# V2.net
KiCad netlist of a schematic drawn in Altium Designer
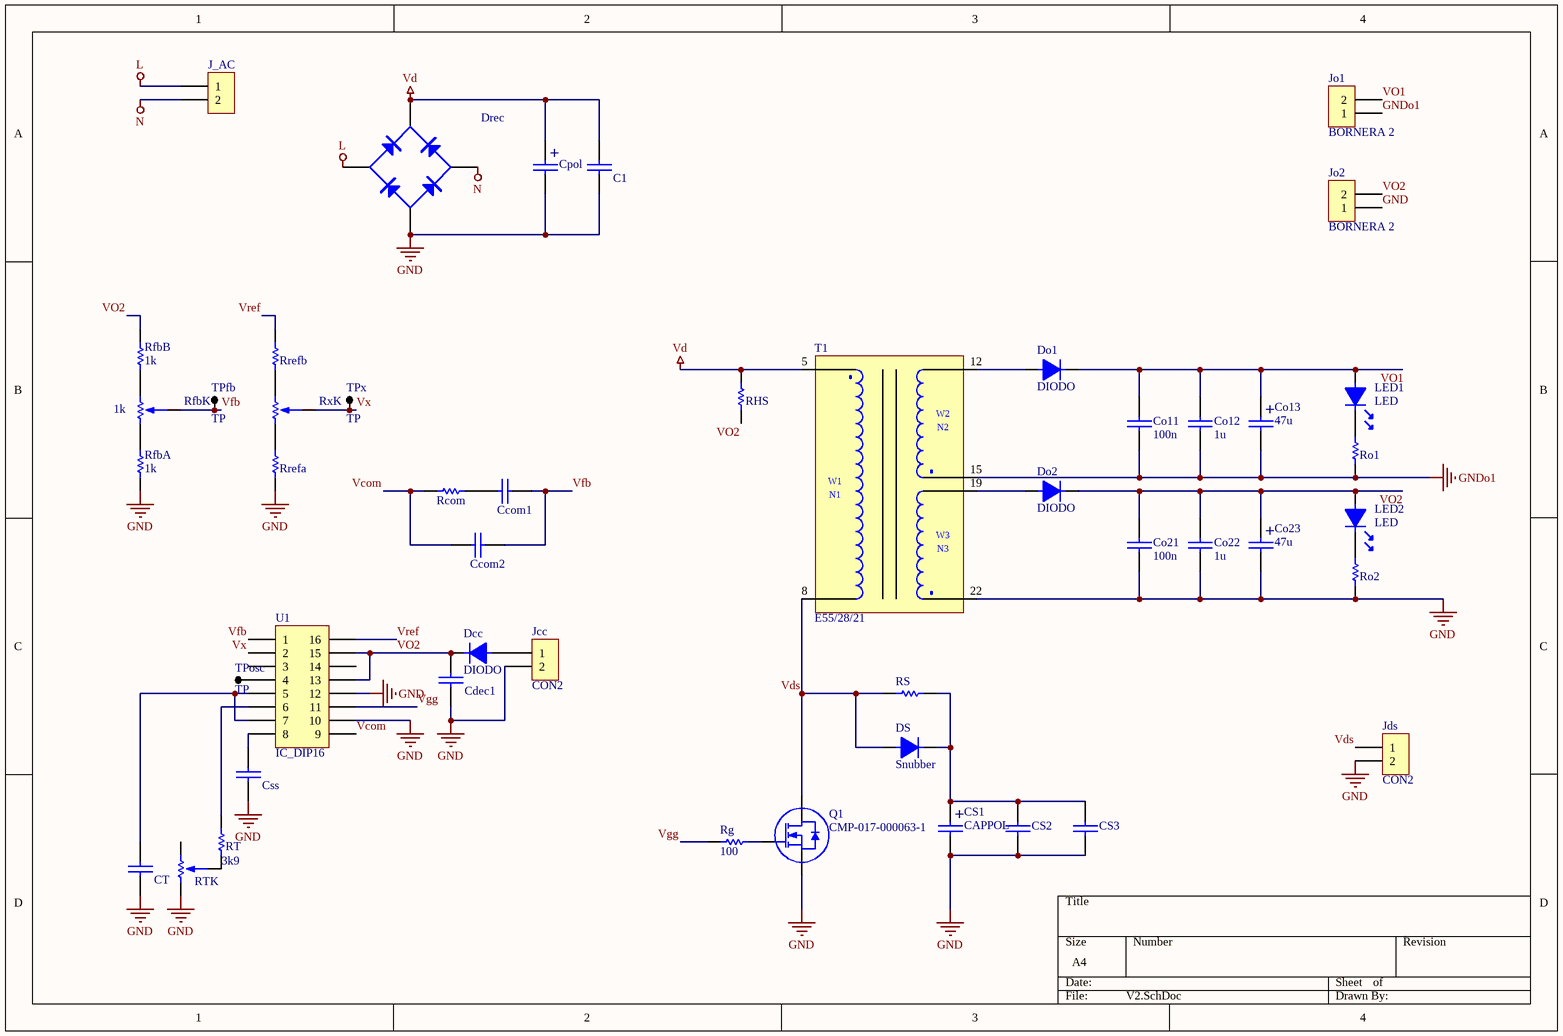
[diagram p0: V2.SchDoc]

(export (version "E")
  (design (tool "Eeschema 10.0.6"))
  (components
    (comp (ref "C1") (value "CAP") (footprint "CAP200") (libsource (lib "Victor Oh") (part "CAP")))
    (comp (ref "Ccom1") (value "CAP") (footprint "CAP200") (libsource (lib "Victor Oh") (part "CAP")))
    (comp (ref "Ccom2") (value "CAP") (footprint "CAP200") (libsource (lib "Victor Oh") (part "CAP")))
    (comp (ref "Cdec1") (value "CAP") (footprint "CAP100") (libsource (lib "Victor Oh") (part "CAP")))
    (comp (ref "Co11") (value "100n") (footprint "CAP200") (libsource (lib "Victor Oh") (part "CAP")))
    (comp (ref "Co12") (value "1u") (footprint "CAP200") (libsource (lib "Victor Oh") (part "CAP")))
    (comp (ref "Co13") (value "47u") (footprint "CAP200RP") (libsource (lib "Victor Oh") (part "CAPPOL")))
    (comp (ref "Co21") (value "100n") (footprint "CAP200") (libsource (lib "Victor Oh") (part "CAP")))
    (comp (ref "Co22") (value "1u") (footprint "CAP200") (libsource (lib "Victor Oh") (part "CAP")))
    (comp (ref "Co23") (value "47u") (footprint "CAP200RP") (libsource (lib "Victor Oh") (part "CAPPOL")))
    (comp (ref "Cpol") (value "CAPPOL") (footprint "CAP200RP2") (libsource (lib "Victor Oh") (part "CAPPOL")))
    (comp (ref "CS1") (value "CAPPOL") (footprint "CAP200RP") (libsource (lib "Victor Oh") (part "CAPPOL")))
    (comp (ref "CS2") (value "~") (footprint "CAP200") (libsource (lib "Victor Oh") (part "CAP")))
    (comp (ref "CS3") (value "~") (footprint "CAP200") (libsource (lib "Victor Oh") (part "CAP")))
    (comp (ref "Css") (value "CAP") (footprint "CAP200") (libsource (lib "Victor Oh") (part "CAP")))
    (comp (ref "CT") (value "2n2") (footprint "CAP200") (libsource (lib "Victor Oh") (part "CAP")))
    (comp (ref "Dcc") (value "DIODO") (footprint "DO41") (libsource (lib "Victor Oh") (part "DIODO")))
    (comp (ref "Do1") (value "DIODO") (footprint "DO41") (libsource (lib "Victor Oh") (part "DIODO")))
    (comp (ref "Do2") (value "DIODO") (footprint "DO41") (libsource (lib "Victor Oh") (part "DIODO")))
    (comp (ref "Drec") (value "~") (footprint "PUENTE - W10M") (libsource (lib "Victor Oh") (part "PUENTE")))
    (comp (ref "DS") (value "Snubber") (footprint "DO41") (libsource (lib "Victor Oh") (part "DIODO")))
    (comp (ref "Jcc") (value "CON2") (footprint "SIP2") (libsource (lib "") (part "BORNERA 2_1")))
    (comp (ref "Jds") (value "CON2") (footprint "SIP2") (libsource (lib "") (part "BORNERA 2_1")))
    (comp (ref "Jo1")
      (value "BORNERA 2")
      (footprint "BORNERA2")
      (libsource (lib "Victor Oh") (part "BORNERA 2"))
    )
    (comp (ref "Jo2")
      (value "BORNERA 2")
      (footprint "BORNERA2")
      (libsource (lib "Victor Oh") (part "BORNERA 2"))
    )
    (comp (ref "J_AC") (value "~") (footprint "BORNERA2") (libsource (lib "") (part "BORNERA 2_1")))
    (comp (ref "LED1") (value "LED") (footprint "LED5") (libsource (lib "Victor Oh") (part "LED")))
    (comp (ref "LED2") (value "LED") (footprint "LED5") (libsource (lib "Victor Oh") (part "LED")))
    (comp (ref "Q1")
      (value "CMP-017-000063-1")
      (footprint "TO-220 V")
      (libsource (lib "Victor Oh") (part "MOSFET N"))
    )
    (comp (ref "Rcom") (value "RES") (footprint "RES400") (libsource (lib "Victor Oh") (part "RES")))
    (comp (ref "RfbA") (value "1k") (footprint "RES400") (libsource (lib "Victor Oh") (part "RES")))
    (comp (ref "RfbB") (value "1k") (footprint "RES400") (libsource (lib "Victor Oh") (part "RES")))
    (comp (ref "RfbK")
      (value "1k")
      (footprint "PRESET V")
      (libsource (lib "Victor Oh") (part "POTENCIOMETRO"))
    )
    (comp (ref "Rg") (value "100") (footprint "RES400") (libsource (lib "Victor Oh") (part "RES")))
    (comp (ref "RHS") (value "100k") (footprint "RES400") (libsource (lib "Victor Oh") (part "RES")))
    (comp (ref "Ro1") (value "RES") (footprint "RES400") (libsource (lib "Victor Oh") (part "RES")))
    (comp (ref "Ro2") (value "RES") (footprint "RES400") (libsource (lib "Victor Oh") (part "RES")))
    (comp (ref "Rrefa") (value "RES") (footprint "RES400") (libsource (lib "Victor Oh") (part "RES")))
    (comp (ref "Rrefb") (value "RES") (footprint "RES400") (libsource (lib "Victor Oh") (part "RES")))
    (comp (ref "RS") (value "~") (footprint "RES400") (libsource (lib "Victor Oh") (part "RES")))
    (comp (ref "RT") (value "3k9") (footprint "RES400") (libsource (lib "Victor Oh") (part "RES")))
    (comp (ref "RTK")
      (value "1k")
      (footprint "PRESET V")
      (libsource (lib "Victor Oh") (part "POTENCIOMETRO"))
    )
    (comp (ref "RxK")
      (value "PRESET")
      (footprint "PRESET V")
      (libsource (lib "Victor Oh") (part "POTENCIOMETRO"))
    )
    (comp (ref "T1")
      (value "E55/28/21")
      (footprint "FlyBack:E55/28/21")
      (description "Transistor E55/28/21")
      (libsource (lib "Flyback") (part "E55/28/21"))
    )
    (comp (ref "TPfb") (value "TP") (footprint "TPTH") (libsource (lib "Victor Oh") (part "TP")))
    (comp (ref "TPosc") (value "TP") (footprint "TPTH") (libsource (lib "Victor Oh") (part "TP")))
    (comp (ref "TPx") (value "TP") (footprint "TPTH") (libsource (lib "Victor Oh") (part "TP")))
    (comp (ref "U1") (value "IC_DIP16") (footprint "DIP16") (libsource (lib "Victor Oh") (part "IC_DIP16")))
  )
  (nets
    (net (code "1") (name "/VO1") (class "Default")
      (node (ref "Co11") (pin "1") (pinfunction "1_1") (pintype "passive"))
      (node (ref "Co12") (pin "1") (pinfunction "1_1") (pintype "passive"))
      (node (ref "Co13") (pin "1") (pinfunction "1_1") (pintype "passive"))
      (node (ref "Do1") (pin "2") (pinfunction "2_2") (pintype "passive"))
      (node (ref "Jo1") (pin "2") (pinfunction "2_2") (pintype "passive"))
      (node (ref "LED1") (pin "1") (pinfunction "1_1") (pintype "passive"))
    )
    (net (code "2") (name "/VO2") (class "Default")
      (node (ref "Cdec1") (pin "1") (pinfunction "1_1") (pintype "passive"))
      (node (ref "Co21") (pin "1") (pinfunction "1_1") (pintype "passive"))
      (node (ref "Co22") (pin "1") (pinfunction "1_1") (pintype "passive"))
      (node (ref "Co23") (pin "1") (pinfunction "1_1") (pintype "passive"))
      (node (ref "Dcc") (pin "2") (pinfunction "2_2") (pintype "passive"))
      (node (ref "Do2") (pin "2") (pinfunction "2_2") (pintype "passive"))
      (node (ref "Jo2") (pin "2") (pinfunction "2_2") (pintype "passive"))
      (node (ref "LED2") (pin "1") (pinfunction "1_1") (pintype "passive"))
      (node (ref "RHS") (pin "1") (pinfunction "1_1") (pintype "passive"))
      (node (ref "RfbB") (pin "2") (pinfunction "2_2") (pintype "passive"))
      (node (ref "U1") (pin "13") (pinfunction "13_13") (pintype "passive"))
      (node (ref "U1") (pin "15") (pinfunction "15_15") (pintype "passive"))
    )
    (net (code "3") (name "/Vcom") (class "Default")
      (node (ref "Ccom2") (pin "1") (pinfunction "1_1") (pintype "passive"))
      (node (ref "Rcom") (pin "1") (pinfunction "1_1") (pintype "passive"))
      (node (ref "U1") (pin "9") (pinfunction "9_9") (pintype "passive"))
    )
    (net (code "4") (name "/Vds") (class "Default")
      (node (ref "DS") (pin "1") (pinfunction "1_1") (pintype "passive"))
      (node (ref "Jds") (pin "1") (pinfunction "1_1") (pintype "passive"))
      (node (ref "Q1") (pin "2") (pinfunction "D_2") (pintype "passive"))
      (node (ref "RS") (pin "1") (pinfunction "1_1") (pintype "passive"))
      (node (ref "T1") (pin "8") (pinfunction "8_8") (pintype "passive"))
    )
    (net (code "5") (name "/Vfb") (class "Default")
      (node (ref "Ccom1") (pin "2") (pinfunction "2_2") (pintype "passive"))
      (node (ref "Ccom2") (pin "2") (pinfunction "2_2") (pintype "passive"))
      (node (ref "RfbK") (pin "2") (pinfunction "2_2") (pintype "passive"))
      (node (ref "TPfb") (pin "1") (pinfunction "1_1") (pintype "passive"))
      (node (ref "U1") (pin "1") (pinfunction "1_1") (pintype "passive"))
    )
    (net (code "6") (name "/Vgg") (class "Default")
      (node (ref "Rg") (pin "1") (pinfunction "1_1") (pintype "passive"))
      (node (ref "U1") (pin "11") (pinfunction "11_11") (pintype "passive"))
    )
    (net (code "7") (name "/Vref") (class "Default")
      (node (ref "Rrefb") (pin "1") (pinfunction "1_1") (pintype "passive"))
      (node (ref "U1") (pin "16") (pinfunction "16_16") (pintype "passive"))
    )
    (net (code "8") (name "/Vx") (class "Default")
      (node (ref "RxK") (pin "2") (pinfunction "2_2") (pintype "passive"))
      (node (ref "TPx") (pin "1") (pinfunction "1_1") (pintype "passive"))
      (node (ref "U1") (pin "2") (pinfunction "2_2") (pintype "passive"))
    )
    (net (code "9") (name "GND") (class "Default")
      (node (ref "C1") (pin "2") (pinfunction "2_2") (pintype "passive"))
      (node (ref "CS1") (pin "2") (pinfunction "2_2") (pintype "passive"))
      (node (ref "CS2") (pin "1") (pinfunction "1_1") (pintype "passive"))
      (node (ref "CS3") (pin "1") (pinfunction "1_1") (pintype "passive"))
      (node (ref "CT") (pin "2") (pinfunction "2_2") (pintype "passive"))
      (node (ref "Cdec1") (pin "2") (pinfunction "2_2") (pintype "passive"))
      (node (ref "Co21") (pin "2") (pinfunction "2_2") (pintype "passive"))
      (node (ref "Co22") (pin "2") (pinfunction "2_2") (pintype "passive"))
      (node (ref "Co23") (pin "2") (pinfunction "2_2") (pintype "passive"))
      (node (ref "Cpol") (pin "2") (pinfunction "2_2") (pintype "passive"))
      (node (ref "Css") (pin "2") (pinfunction "2_2") (pintype "passive"))
      (node (ref "Drec") (pin "3") (pinfunction "V-_3") (pintype "passive"))
      (node (ref "Jcc") (pin "2") (pinfunction "2_2") (pintype "passive"))
      (node (ref "Jds") (pin "2") (pinfunction "2_2") (pintype "passive"))
      (node (ref "Jo2") (pin "1") (pinfunction "1_1") (pintype "passive"))
      (node (ref "Q1") (pin "3") (pinfunction "S_3") (pintype "passive"))
      (node (ref "RTK") (pin "3") (pinfunction "3_3") (pintype "passive"))
      (node (ref "RfbA") (pin "1") (pinfunction "1_1") (pintype "passive"))
      (node (ref "Ro2") (pin "2") (pinfunction "2_2") (pintype "passive"))
      (node (ref "Rrefa") (pin "2") (pinfunction "2_2") (pintype "passive"))
      (node (ref "T1") (pin "22") (pinfunction "22_22") (pintype "passive"))
      (node (ref "U1") (pin "10") (pinfunction "10_10") (pintype "passive"))
      (node (ref "U1") (pin "12") (pinfunction "12_12") (pintype "passive"))
    )
    (net (code "10") (name "GNDo1") (class "Default")
      (node (ref "Co11") (pin "2") (pinfunction "2_2") (pintype "passive"))
      (node (ref "Co12") (pin "2") (pinfunction "2_2") (pintype "passive"))
      (node (ref "Co13") (pin "2") (pinfunction "2_2") (pintype "passive"))
      (node (ref "Jo1") (pin "1") (pinfunction "1_1") (pintype "passive"))
      (node (ref "Ro1") (pin "1") (pinfunction "1_1") (pintype "passive"))
      (node (ref "T1") (pin "15") (pinfunction "15_15") (pintype "passive"))
    )
    (net (code "11") (name "L") (class "Default")
      (node (ref "Drec") (pin "2") (pinfunction "AC_2") (pintype "passive"))
      (node (ref "J_AC") (pin "1") (pinfunction "1_1") (pintype "passive"))
    )
    (net (code "12") (name "N") (class "Default")
      (node (ref "Drec") (pin "4") (pinfunction "AC_4") (pintype "passive"))
      (node (ref "J_AC") (pin "2") (pinfunction "2_2") (pintype "passive"))
    )
    (net (code "13") (name "Net-(CS1-Pad1)") (class "Default")
      (node (ref "CS1") (pin "1") (pinfunction "1_1") (pintype "passive"))
      (node (ref "CS2") (pin "2") (pinfunction "2_2") (pintype "passive"))
      (node (ref "CS3") (pin "2") (pinfunction "2_2") (pintype "passive"))
      (node (ref "DS") (pin "2") (pinfunction "2_2") (pintype "passive"))
      (node (ref "RS") (pin "2") (pinfunction "2_2") (pintype "passive"))
    )
    (net (code "14") (name "Net-(CT-Pad1)") (class "Default")
      (node (ref "CT") (pin "1") (pinfunction "1_1") (pintype "passive"))
      (node (ref "U1") (pin "5") (pinfunction "5_5") (pintype "passive"))
      (node (ref "U1") (pin "7") (pinfunction "7_7") (pintype "passive"))
    )
    (net (code "15") (name "Net-(Ccom1-Pad1)") (class "Default")
      (node (ref "Ccom1") (pin "1") (pinfunction "1_1") (pintype "passive"))
      (node (ref "Rcom") (pin "2") (pinfunction "2_2") (pintype "passive"))
    )
    (net (code "16") (name "Net-(Css-Pad1)") (class "Default")
      (node (ref "Css") (pin "1") (pinfunction "1_1") (pintype "passive"))
      (node (ref "U1") (pin "8") (pinfunction "8_8") (pintype "passive"))
    )
    (net (code "17") (name "Net-(Dcc-Pad1)") (class "Default")
      (node (ref "Dcc") (pin "1") (pinfunction "1_1") (pintype "passive"))
      (node (ref "Jcc") (pin "1") (pinfunction "1_1") (pintype "passive"))
    )
    (net (code "18") (name "Net-(Do1-Pad1)") (class "Default")
      (node (ref "Do1") (pin "1") (pinfunction "1_1") (pintype "passive"))
      (node (ref "T1") (pin "12") (pinfunction "12_12") (pintype "passive"))
    )
    (net (code "19") (name "Net-(Do2-Pad1)") (class "Default")
      (node (ref "Do2") (pin "1") (pinfunction "1_1") (pintype "passive"))
      (node (ref "T1") (pin "19") (pinfunction "19_19") (pintype "passive"))
    )
    (net (code "20") (name "Net-(LED1-Pad2)") (class "Default")
      (node (ref "LED1") (pin "2") (pinfunction "2_2") (pintype "passive"))
      (node (ref "Ro1") (pin "2") (pinfunction "2_2") (pintype "passive"))
    )
    (net (code "21") (name "Net-(LED2-Pad2)") (class "Default")
      (node (ref "LED2") (pin "2") (pinfunction "2_2") (pintype "passive"))
      (node (ref "Ro2") (pin "1") (pinfunction "1_1") (pintype "passive"))
    )
    (net (code "22") (name "Net-(Q1-G)") (class "Default")
      (node (ref "Q1") (pin "1") (pinfunction "G_1") (pintype "passive"))
      (node (ref "Rg") (pin "2") (pinfunction "2_2") (pintype "passive"))
    )
    (net (code "23") (name "Net-(RT-Pad1)") (class "Default")
      (node (ref "RT") (pin "1") (pinfunction "1_1") (pintype "passive"))
      (node (ref "U1") (pin "6") (pinfunction "6_6") (pintype "passive"))
    )
    (net (code "24") (name "Net-(RT-Pad2)") (class "Default")
      (node (ref "RT") (pin "2") (pinfunction "2_2") (pintype "passive"))
      (node (ref "RTK") (pin "2") (pinfunction "2_2") (pintype "passive"))
    )
    (net (code "25") (name "Net-(RfbA-Pad2)") (class "Default")
      (node (ref "RfbA") (pin "2") (pinfunction "2_2") (pintype "passive"))
      (node (ref "RfbK") (pin "3") (pinfunction "3_3") (pintype "passive"))
    )
    (net (code "26") (name "Net-(RfbB-Pad1)") (class "Default")
      (node (ref "RfbB") (pin "1") (pinfunction "1_1") (pintype "passive"))
      (node (ref "RfbK") (pin "1") (pinfunction "1_1") (pintype "passive"))
    )
    (net (code "27") (name "Net-(Rrefa-Pad1)") (class "Default")
      (node (ref "Rrefa") (pin "1") (pinfunction "1_1") (pintype "passive"))
      (node (ref "RxK") (pin "3") (pinfunction "3_3") (pintype "passive"))
    )
    (net (code "28") (name "Net-(Rrefb-Pad2)") (class "Default")
      (node (ref "Rrefb") (pin "2") (pinfunction "2_2") (pintype "passive"))
      (node (ref "RxK") (pin "1") (pinfunction "1_1") (pintype "passive"))
    )
    (net (code "29") (name "Net-(TPosc-Pad1)") (class "Default")
      (node (ref "TPosc") (pin "1") (pinfunction "1_1") (pintype "passive"))
      (node (ref "U1") (pin "4") (pinfunction "4_4") (pintype "passive"))
    )
    (net (code "30") (name "Vd") (class "Default")
      (node (ref "C1") (pin "1") (pinfunction "1_1") (pintype "passive"))
      (node (ref "Cpol") (pin "1") (pinfunction "1_1") (pintype "passive"))
      (node (ref "Drec") (pin "1") (pinfunction "V+_1") (pintype "passive"))
      (node (ref "RHS") (pin "2") (pinfunction "2_2") (pintype "passive"))
      (node (ref "T1") (pin "5") (pinfunction "5_5") (pintype "passive"))
    )
    (net (code "31") (name "unconnected-(RTK-Pad1)") (class "Default")
      (node (ref "RTK") (pin "1") (pinfunction "1_1") (pintype "passive"))
    )
    (net (code "32") (name "unconnected-(U1-Pad3)") (class "Default")
      (node (ref "U1") (pin "3") (pinfunction "3_3") (pintype "passive"))
    )
    (net (code "33") (name "unconnected-(U1-Pad14)") (class "Default")
      (node (ref "U1") (pin "14") (pinfunction "14_14") (pintype "passive"))
    )
  )
)
